# 2_Power.net
KiCad netlist of a schematic drawn in Altium Designer
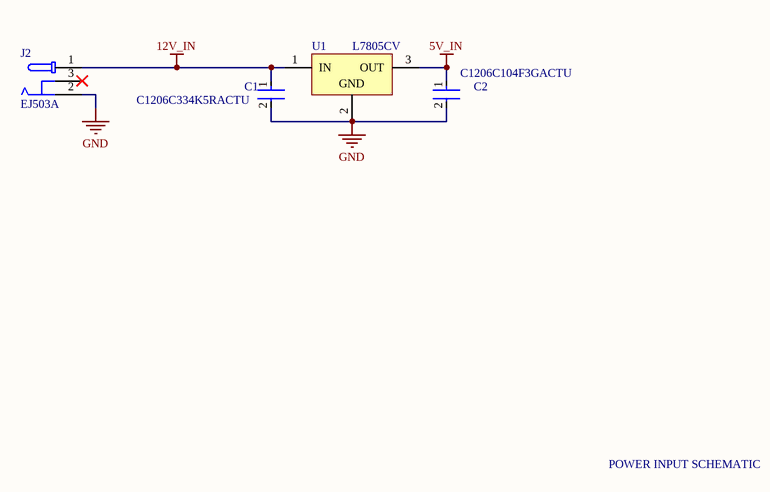
[diagram p0: 2_Power.SchDoc]

(export (version "E")
  (design (tool "Eeschema 10.0.6"))
  (components
    (comp (ref "C1")
      (value "C1206C334K5RACTU")
      (footprint "FP-C1206C-EB-MFG")
      (description "CAP CER 0.33UF 50V X7R 1206")
      (fields
        (field (name "OCTOPART") "https://octopart.com/c1206c334k5ractu-kemet-146059")
        (field (name "TOLERANCE") "0.1")
      )
      (libsource (lib "Altium Content Vault") (part "b4654b650e69147ec39a6b967a45e02"))
    )
    (comp (ref "C2")
      (value "C1206C104F3GACTU")
      (footprint "FP-C1206C-EB-MFG")
      (description "CAP CER 0.1UF 25V C0G/NP0 1206")
      (fields (field (name "MANUFACTURER") "KEMET") (field (name "TOLERANCE") "0.01"))
      (libsource (lib "Altium Content Vault") (part "b4654b650e69147ec39a6b967a45e02"))
    )
    (comp (ref "J2")
      (value "EJ503A")
      (footprint "MPD_EJ503A")
      (description "Power Barrel Connector Jack 2.10mm ID (0.083), 5.50mm OD (0.217) Through Hole, Right Angle")
      (fields (field (name "MF") "MPD"))
      (libsource (lib "McMaster University") (part "EJ503A"))
    )
    (comp (ref "U1")
      (value "L7805CV")
      (footprint "TO220")
      (description "Positive Voltage Regulator, 5V, 3-Pin TO-220")
      (libsource (lib "Altium Content Vault") (part "PM-REG-L4940-SIL3"))
    )
  )
  (nets
    (net (code "1") (name "5V_IN") (class "Default")
      (node (ref "C2") (pin "1") (pinfunction "1_1") (pintype "passive"))
      (node (ref "U1") (pin "3") (pinfunction "OUT_3") (pintype "power_in"))
    )
    (net (code "2") (name "12V_IN") (class "Default")
      (node (ref "C1") (pin "1") (pinfunction "1_1") (pintype "passive"))
      (node (ref "J2") (pin "1") (pinfunction "1_1") (pintype "passive"))
      (node (ref "U1") (pin "1") (pinfunction "IN_1") (pintype "power_in"))
    )
    (net (code "3") (name "GND") (class "Default")
      (node (ref "C1") (pin "2") (pinfunction "2_2") (pintype "passive"))
      (node (ref "C2") (pin "2") (pinfunction "2_2") (pintype "passive"))
      (node (ref "J2") (pin "2") (pinfunction "2_2") (pintype "passive"))
      (node (ref "U1") (pin "2") (pinfunction "GND_2") (pintype "power_in"))
    )
    (net (code "4") (name "unconnected-(J2-Pad3)") (class "Default")
      (node (ref "J2") (pin "3") (pinfunction "3_3") (pintype "passive+no_connect"))
    )
  )
)
